# exemplo_pratico_2.net
KiCad netlist of a schematic drawn in EAGLE
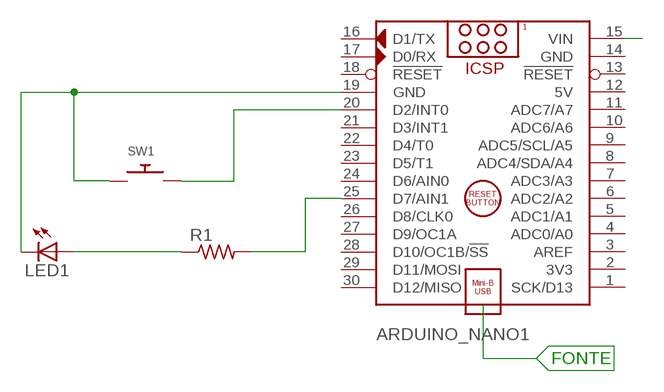
[diagram p0: schematic, sheet 1]

(export (version "E")
  (design (tool "Eeschema 10.0.6"))
  (components
    (comp (ref "ARDUINO_NANO1")
      (value "ARDUINO_NANO")
      (footprint "eagle-import:ARDUINO_NANO")
      (libsource (lib "eagle-import") (part "ARDUINO_NANO"))
    )
    (comp (ref "LED1")
      (value "LED3MM")
      (footprint "eagle-import:LED3MM")
      (libsource (lib "eagle-import") (part "LED3MM"))
    )
    (comp (ref "R1")
      (value "R-US_FLIPFLOP")
      (footprint "eagle-import:0805-THM")
      (libsource (lib "eagle-import") (part "R-US_FLIPFLOP"))
    )
    (comp (ref "SW1")
      (value "SWITCH_PUSHBUTTONEVQ-PE")
      (footprint "eagle-import:TACT_PANA-EVQ")
      (libsource (lib "eagle-import") (part "SWITCH_PUSHBUTTONEVQ-PE"))
    )
  )
  (nets
    (net (code "1") (name "/5V") (class "Default")
      (node (ref "ARDUINO_NANO1") (pin "12") (pinfunction "5V_12") (pintype "power_in"))
    )
    (net (code "2") (name "/GND") (class "Default")
      (node (ref "ARDUINO_NANO1") (pin "14") (pinfunction "GND_14") (pintype "power_in"))
    )
    (net (code "4") (name "Net-(ARDUINO_NANO1-D2{slash}INT0)") (class "Default")
      (node (ref "ARDUINO_NANO1") (pin "20") (pinfunction "D2/INT0_20") (pintype "bidirectional"))
      (node (ref "SW1") (pin "P$2") (pinfunction "P$2_P$2") (pintype "passive"))
    )
    (net (code "5") (name "Net-(ARDUINO_NANO1-D7{slash}AIN1)") (class "Default")
      (node (ref "ARDUINO_NANO1") (pin "25") (pinfunction "D7/AIN1_25") (pintype "bidirectional"))
      (node (ref "R1") (pin "2") (pinfunction "2_2") (pintype "passive"))
    )
    (net (code "6") (name "Net-(LED1-C)") (class "Default")
      (node (ref "ARDUINO_NANO1") (pin "19") (pinfunction "GND_19") (pintype "power_in"))
      (node (ref "LED1") (pin "K") (pinfunction "C_K") (pintype "passive"))
      (node (ref "SW1") (pin "P$1") (pinfunction "P$1_P$1") (pintype "passive"))
    )
    (net (code "7") (name "Net-(LED1-PadA)") (class "Default")
      (node (ref "LED1") (pin "A") (pinfunction "A_A") (pintype "passive"))
      (node (ref "R1") (pin "1") (pinfunction "1_1") (pintype "passive"))
    )
    (net (code "8") (name "unconnected-(ARDUINO_NANO1-3V3-Pad2)") (class "Default")
      (node (ref "ARDUINO_NANO1") (pin "2") (pinfunction "3V3_2") (pintype "output"))
    )
    (net (code "9") (name "unconnected-(ARDUINO_NANO1-ADC0{slash}A0-Pad4)") (class "Default")
      (node (ref "ARDUINO_NANO1") (pin "4") (pinfunction "ADC0/A0_4") (pintype "bidirectional"))
    )
    (net (code "10") (name "unconnected-(ARDUINO_NANO1-ADC1{slash}A1-Pad5)") (class "Default")
      (node (ref "ARDUINO_NANO1") (pin "5") (pinfunction "ADC1/A1_5") (pintype "bidirectional"))
    )
    (net (code "11") (name "unconnected-(ARDUINO_NANO1-ADC2{slash}A2-Pad6)") (class "Default")
      (node (ref "ARDUINO_NANO1") (pin "6") (pinfunction "ADC2/A2_6") (pintype "bidirectional"))
    )
    (net (code "12") (name "unconnected-(ARDUINO_NANO1-ADC3{slash}A3-Pad7)") (class "Default")
      (node (ref "ARDUINO_NANO1") (pin "7") (pinfunction "ADC3/A3_7") (pintype "bidirectional"))
    )
    (net (code "13") (name "unconnected-(ARDUINO_NANO1-ADC4{slash}SDA{slash}A4-Pad8)") (class "Default")
      (node (ref "ARDUINO_NANO1") (pin "8") (pinfunction "ADC4/SDA/A4_8") (pintype "bidirectional"))
    )
    (net (code "14") (name "unconnected-(ARDUINO_NANO1-ADC5{slash}SCL{slash}A5-Pad9)") (class "Default")
      (node (ref "ARDUINO_NANO1") (pin "9") (pinfunction "ADC5/SCL/A5_9") (pintype "bidirectional"))
    )
    (net (code "15") (name "unconnected-(ARDUINO_NANO1-ADC6{slash}A6-Pad10)") (class "Default")
      (node (ref "ARDUINO_NANO1") (pin "10") (pinfunction "ADC6/A6_10") (pintype "bidirectional"))
    )
    (net (code "16") (name "unconnected-(ARDUINO_NANO1-ADC7{slash}A7-Pad11)") (class "Default")
      (node (ref "ARDUINO_NANO1") (pin "11") (pinfunction "ADC7/A7_11") (pintype "bidirectional"))
    )
    (net (code "17") (name "unconnected-(ARDUINO_NANO1-AREF-Pad3)") (class "Default")
      (node (ref "ARDUINO_NANO1") (pin "3") (pinfunction "AREF_3") (pintype "input"))
    )
    (net (code "18") (name "unconnected-(ARDUINO_NANO1-D0{slash}RX-Pad17)") (class "Default")
      (node (ref "ARDUINO_NANO1") (pin "17") (pinfunction "D0/RX_17") (pintype "bidirectional"))
    )
    (net (code "19") (name "unconnected-(ARDUINO_NANO1-D1{slash}TX-Pad16)") (class "Default")
      (node (ref "ARDUINO_NANO1") (pin "16") (pinfunction "D1/TX_16") (pintype "bidirectional"))
    )
    (net (code "20") (name "unconnected-(ARDUINO_NANO1-D3{slash}INT1-Pad21)") (class "Default")
      (node (ref "ARDUINO_NANO1") (pin "21") (pinfunction "D3/INT1_21") (pintype "bidirectional"))
    )
    (net (code "21") (name "unconnected-(ARDUINO_NANO1-D4{slash}T0-Pad22)") (class "Default")
      (node (ref "ARDUINO_NANO1") (pin "22") (pinfunction "D4/T0_22") (pintype "bidirectional"))
    )
    (net (code "22") (name "unconnected-(ARDUINO_NANO1-D5{slash}T1-Pad23)") (class "Default")
      (node (ref "ARDUINO_NANO1") (pin "23") (pinfunction "D5/T1_23") (pintype "bidirectional"))
    )
    (net (code "23") (name "unconnected-(ARDUINO_NANO1-D6{slash}AIN0-Pad24)") (class "Default")
      (node (ref "ARDUINO_NANO1") (pin "24") (pinfunction "D6/AIN0_24") (pintype "bidirectional"))
    )
    (net (code "24") (name "unconnected-(ARDUINO_NANO1-D8{slash}CLK0-Pad26)") (class "Default")
      (node (ref "ARDUINO_NANO1") (pin "26") (pinfunction "D8/CLK0_26") (pintype "bidirectional"))
    )
    (net (code "25") (name "unconnected-(ARDUINO_NANO1-D9{slash}OC1A-Pad27)") (class "Default")
      (node (ref "ARDUINO_NANO1") (pin "27") (pinfunction "D9/OC1A_27") (pintype "bidirectional"))
    )
    (net (code "26") (name "unconnected-(ARDUINO_NANO1-D10{slash}OC1B{slash}~{SS}-Pad28)") (class "Default")
      (node (ref "ARDUINO_NANO1") (pin "28") (pinfunction "D10/OC1B/~{SS}_28") (pintype "bidirectional"))
    )
    (net (code "27") (name "unconnected-(ARDUINO_NANO1-D11{slash}MOSI-Pad29)") (class "Default")
      (node (ref "ARDUINO_NANO1") (pin "29") (pinfunction "D11/MOSI_29") (pintype "bidirectional"))
    )
    (net (code "28") (name "unconnected-(ARDUINO_NANO1-D12{slash}MISO-Pad30)") (class "Default")
      (node (ref "ARDUINO_NANO1") (pin "30") (pinfunction "D12/MISO_30") (pintype "bidirectional"))
    )
    (net (code "29") (name "unconnected-(ARDUINO_NANO1-SCK{slash}D13-Pad1)") (class "Default")
      (node (ref "ARDUINO_NANO1") (pin "1") (pinfunction "SCK/D13_1") (pintype "bidirectional"))
    )
    (net (code "30") (name "unconnected-(ARDUINO_NANO1-VIN-Pad15)") (class "Default")
      (node (ref "ARDUINO_NANO1") (pin "15") (pinfunction "VIN_15") (pintype "power_in"))
    )
    (net (code "31") (name "unconnected-(ARDUINO_NANO1-~{RESET}-Pad13)") (class "Default")
      (node (ref "ARDUINO_NANO1") (pin "13") (pinfunction "~{RESET}_13") (pintype "input"))
    )
    (net (code "32") (name "unconnected-(ARDUINO_NANO1-~{RESET}-Pad18)") (class "Default")
      (node (ref "ARDUINO_NANO1") (pin "18") (pinfunction "~{RESET}_18") (pintype "input"))
    )
  )
)
